# ECUEXT1_23.net
KiCad netlist of a schematic drawn in Altium Designer
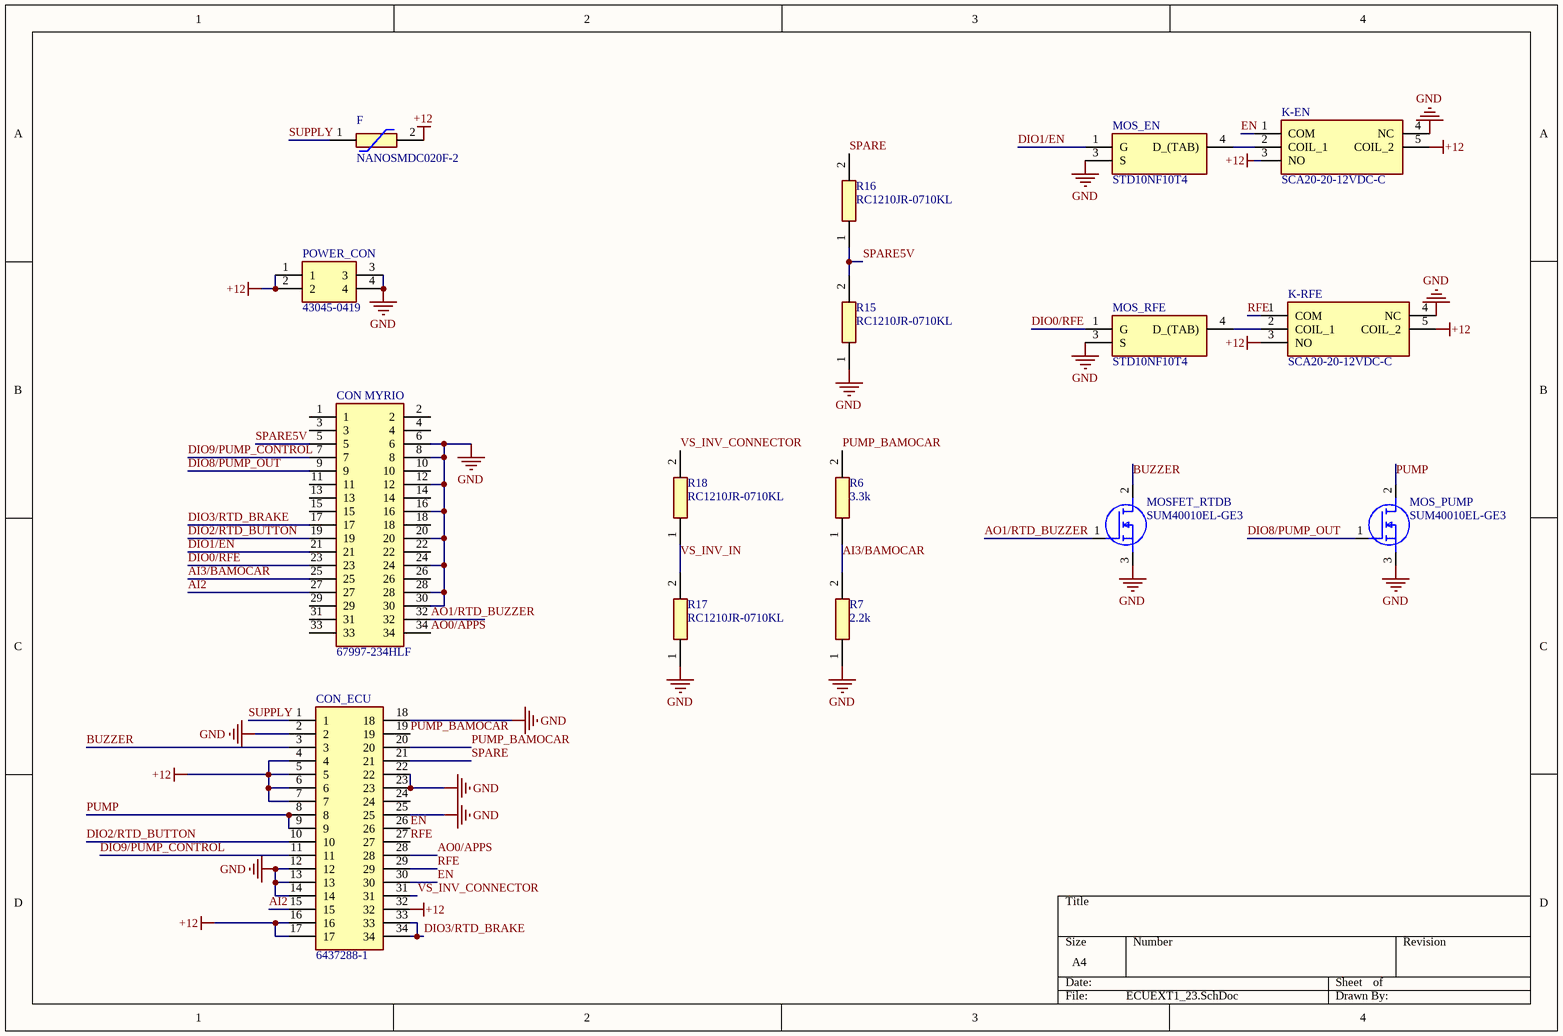
[diagram p0: ECUEXT1_23.SchDoc]

(export (version "E")
  (design (tool "Eeschema 10.0.6"))
  (components
    (comp (ref "CON MYRIO")
      (value "67997-234HLF")
      (footprint "SamacSys:HDRV34W67P254_2X17_4318X483X858P")
      (description "Connector")
      (fields (field (name "MOUSER PART NUMBER") "649-67997-234HLF"))
      (libsource (lib "*") (part "67997-234HLF"))
    )
    (comp (ref "CON_ECU")
      (value "6437288-1")
      (footprint "SamacSys:6437288-1")
      (description "Connector")
      (fields (field (name "MOUSER PART NUMBER") "571-6437288-1"))
      (libsource (lib "SamacSys") (part "6437288-1"))
    )
    (comp (ref "F")
      (value "NANOSMDC020F-2")
      (footprint "SamacSys:NANOSMDC016F2")
      (description "Resettable Fuse")
      (fields (field (name "MOUSER PART NUMBER") "650-NANOSMDC020F-2"))
      (libsource (lib "*") (part "NANOSMDC020F-2"))
    )
    (comp (ref "K-EN")
      (value "SCA20-20-12VDC-C")
      (footprint "SamacSys:SCA202012VDCC")
      (description "Relay or Contactor")
      (libsource (lib "SamacSys") (part "SCA20-20-12VDC-C"))
    )
    (comp (ref "K-RFE")
      (value "SCA20-20-12VDC-C")
      (footprint "SamacSys:SCA202012VDCC")
      (description "Relay or Contactor")
      (libsource (lib "SamacSys") (part "SCA20-20-12VDC-C"))
    )
    (comp (ref "MOSFET_RTDB")
      (value "SUM40010EL-GE3")
      (footprint "SamacSys:SUM40010ELGE3")
      (description "MOSFET (N-Channel)")
      (fields (field (name "MOUSER PART NUMBER") "78-SUM40010EL-GE3"))
      (libsource (lib "SamacSys") (part "SUM40010EL-GE3"))
    )
    (comp (ref "MOS_EN")
      (value "STD10NF10T4")
      (footprint "SamacSys:TO228P972X240-3N")
      (description "Integrated Circuit")
      (fields (field (name "MOUSER PART NUMBER") "511-STD10NF10"))
      (libsource (lib "SamacSys") (part "STD10NF10T4"))
    )
    (comp (ref "MOS_PUMP")
      (value "SUM40010EL-GE3")
      (footprint "SamacSys:SUM40010ELGE3")
      (description "MOSFET (N-Channel)")
      (fields (field (name "MOUSER PART NUMBER") "78-SUM40010EL-GE3"))
      (libsource (lib "SamacSys") (part "SUM40010EL-GE3"))
    )
    (comp (ref "MOS_RFE")
      (value "STD10NF10T4")
      (footprint "SamacSys:TO228P972X240-3N")
      (description "Integrated Circuit")
      (fields (field (name "MOUSER PART NUMBER") "511-STD10NF10"))
      (libsource (lib "SamacSys") (part "STD10NF10T4"))
    )
    (comp (ref "POWER_CON")
      (value "43045-0419")
      (footprint "SamacSys:43045-04YY_181920")
      (description "Connector")
      (fields (field (name "MOUSER PART NUMBER") "538-43045-0419"))
      (libsource (lib "SamacSys") (part "43045-0419"))
    )
    (comp (ref "R6")
      (value "3.3k")
      (footprint "SamacSys:RESC3126X60N")
      (description "Resistor")
      (fields
        (field (name "MANUFACTURER_PART_NUMBER") "RC1210JR-0710KL")
        (field (name "MOUSER PART NUMBER") "603-RC1210JR-0710KL")
      )
      (libsource (lib "*") (part "RC1210JR-0710KL"))
    )
    (comp (ref "R7")
      (value "2.2k")
      (footprint "SamacSys:RESC3126X60N")
      (description "Resistor")
      (fields
        (field (name "MANUFACTURER_PART_NUMBER") "RC1210JR-0710KL")
        (field (name "MOUSER PART NUMBER") "603-RC1210JR-0710KL")
      )
      (libsource (lib "*") (part "RC1210JR-0710KL"))
    )
    (comp (ref "R15")
      (value "RC1210JR-0710KL")
      (footprint "SamacSys:RESC3126X60N")
      (description "Resistor")
      (fields (field (name "MOUSER PART NUMBER") "603-RC1210JR-0710KL"))
      (libsource (lib "SamacSys") (part "RC1210JR-0710KL"))
    )
    (comp (ref "R16")
      (value "RC1210JR-0710KL")
      (footprint "SamacSys:RESC3126X60N")
      (description "Resistor")
      (fields (field (name "MOUSER PART NUMBER") "603-RC1210JR-0710KL"))
      (libsource (lib "SamacSys") (part "RC1210JR-0710KL"))
    )
    (comp (ref "R17")
      (value "RC1210JR-0710KL")
      (footprint "SamacSys:RESC3126X60N")
      (description "Resistor")
      (fields (field (name "MOUSER PART NUMBER") "603-RC1210JR-0710KL"))
      (libsource (lib "SamacSys") (part "RC1210JR-0710KL"))
    )
    (comp (ref "R18")
      (value "RC1210JR-0710KL")
      (footprint "SamacSys:RESC3126X60N")
      (description "Resistor")
      (fields (field (name "MOUSER PART NUMBER") "603-RC1210JR-0710KL"))
      (libsource (lib "SamacSys") (part "RC1210JR-0710KL"))
    )
  )
  (nets
    (net (code "1") (name "+12") (class "Default")
      (node (ref "CON_ECU") (pin "16") (pinfunction "16_16") (pintype "passive"))
      (node (ref "CON_ECU") (pin "17") (pinfunction "17_17") (pintype "passive"))
      (node (ref "CON_ECU") (pin "32") (pinfunction "32_32") (pintype "passive"))
      (node (ref "CON_ECU") (pin "4") (pinfunction "4_4") (pintype "passive"))
      (node (ref "CON_ECU") (pin "5") (pinfunction "5_5") (pintype "passive"))
      (node (ref "CON_ECU") (pin "6") (pinfunction "6_6") (pintype "passive"))
      (node (ref "CON_ECU") (pin "7") (pinfunction "7_7") (pintype "passive"))
      (node (ref "F") (pin "2") (pinfunction "2_2") (pintype "passive"))
      (node (ref "K-EN") (pin "3") (pinfunction "NO_3") (pintype "passive"))
      (node (ref "K-EN") (pin "5") (pinfunction "COIL_2_5") (pintype "passive"))
      (node (ref "K-RFE") (pin "3") (pinfunction "NO_3") (pintype "passive"))
      (node (ref "K-RFE") (pin "5") (pinfunction "COIL_2_5") (pintype "passive"))
      (node (ref "POWER_CON") (pin "1") (pinfunction "1_1") (pintype "passive"))
      (node (ref "POWER_CON") (pin "2") (pinfunction "2_2") (pintype "passive"))
    )
    (net (code "2") (name "/AI2") (class "Default")
      (node (ref "CON MYRIO") (pin "27") (pinfunction "27_27") (pintype "passive"))
      (node (ref "CON_ECU") (pin "15") (pinfunction "15_15") (pintype "passive"))
    )
    (net (code "3") (name "/AI3{slash}BAMOCAR") (class "Default")
      (node (ref "CON MYRIO") (pin "25") (pinfunction "25_25") (pintype "passive"))
      (node (ref "R6") (pin "1") (pinfunction "1_1") (pintype "passive"))
      (node (ref "R7") (pin "2") (pinfunction "2_2") (pintype "passive"))
    )
    (net (code "4") (name "/AO0{slash}APPS") (class "Default")
      (node (ref "CON MYRIO") (pin "34") (pinfunction "34_34") (pintype "passive"))
      (node (ref "CON_ECU") (pin "28") (pinfunction "28_28") (pintype "passive"))
    )
    (net (code "5") (name "/AO1{slash}RTD_BUZZER") (class "Default")
      (node (ref "CON MYRIO") (pin "32") (pinfunction "32_32") (pintype "passive"))
      (node (ref "MOSFET_RTDB") (pin "1") (pinfunction "G_1") (pintype "passive"))
    )
    (net (code "6") (name "/BUZZER") (class "Default")
      (node (ref "CON_ECU") (pin "3") (pinfunction "3_3") (pintype "passive"))
      (node (ref "MOSFET_RTDB") (pin "2") (pinfunction "D_2") (pintype "passive"))
    )
    (net (code "7") (name "/DIO0{slash}RFE") (class "Default")
      (node (ref "CON MYRIO") (pin "23") (pinfunction "23_23") (pintype "passive"))
      (node (ref "MOS_RFE") (pin "1") (pinfunction "G_1") (pintype "passive"))
    )
    (net (code "8") (name "/DIO1{slash}EN") (class "Default")
      (node (ref "CON MYRIO") (pin "21") (pinfunction "21_21") (pintype "passive"))
      (node (ref "MOS_EN") (pin "1") (pinfunction "G_1") (pintype "passive"))
    )
    (net (code "9") (name "/DIO2{slash}RTD_BUTTON") (class "Default")
      (node (ref "CON MYRIO") (pin "19") (pinfunction "19_19") (pintype "passive"))
      (node (ref "CON_ECU") (pin "10") (pinfunction "10_10") (pintype "passive"))
    )
    (net (code "10") (name "/DIO3{slash}RTD_BRAKE") (class "Default")
      (node (ref "CON MYRIO") (pin "17") (pinfunction "17_17") (pintype "passive"))
      (node (ref "CON_ECU") (pin "33") (pinfunction "33_33") (pintype "passive"))
      (node (ref "CON_ECU") (pin "34") (pinfunction "34_34") (pintype "passive"))
    )
    (net (code "11") (name "/DIO8{slash}PUMP_OUT") (class "Default")
      (node (ref "CON MYRIO") (pin "9") (pinfunction "9_9") (pintype "passive"))
      (node (ref "MOS_PUMP") (pin "1") (pinfunction "G_1") (pintype "passive"))
    )
    (net (code "12") (name "/DIO9{slash}PUMP_CONTROL") (class "Default")
      (node (ref "CON MYRIO") (pin "7") (pinfunction "7_7") (pintype "passive"))
      (node (ref "CON_ECU") (pin "11") (pinfunction "11_11") (pintype "passive"))
    )
    (net (code "13") (name "/EN") (class "Default")
      (node (ref "CON_ECU") (pin "26") (pinfunction "26_26") (pintype "passive"))
      (node (ref "CON_ECU") (pin "30") (pinfunction "30_30") (pintype "passive"))
      (node (ref "K-EN") (pin "1") (pinfunction "COM_1") (pintype "passive"))
    )
    (net (code "14") (name "/PUMP") (class "Default")
      (node (ref "CON_ECU") (pin "8") (pinfunction "8_8") (pintype "passive"))
      (node (ref "CON_ECU") (pin "9") (pinfunction "9_9") (pintype "passive"))
      (node (ref "MOS_PUMP") (pin "2") (pinfunction "D_2") (pintype "passive"))
    )
    (net (code "15") (name "/PUMP_BAMOCAR") (class "Default")
      (node (ref "CON_ECU") (pin "19") (pinfunction "19_19") (pintype "passive"))
      (node (ref "CON_ECU") (pin "20") (pinfunction "20_20") (pintype "passive"))
      (node (ref "R6") (pin "2") (pinfunction "2_2") (pintype "passive"))
    )
    (net (code "16") (name "/RFE") (class "Default")
      (node (ref "CON_ECU") (pin "27") (pinfunction "27_27") (pintype "passive"))
      (node (ref "CON_ECU") (pin "29") (pinfunction "29_29") (pintype "passive"))
      (node (ref "K-RFE") (pin "1") (pinfunction "COM_1") (pintype "passive"))
    )
    (net (code "17") (name "/SPARE") (class "Default")
      (node (ref "CON_ECU") (pin "21") (pinfunction "21_21") (pintype "passive"))
      (node (ref "R16") (pin "2") (pinfunction "2_2") (pintype "passive"))
    )
    (net (code "18") (name "/SPARE5V") (class "Default")
      (node (ref "CON MYRIO") (pin "5") (pinfunction "5_5") (pintype "passive"))
      (node (ref "R15") (pin "2") (pinfunction "2_2") (pintype "passive"))
      (node (ref "R16") (pin "1") (pinfunction "1_1") (pintype "passive"))
    )
    (net (code "19") (name "/SUPPLY") (class "Default")
      (node (ref "CON_ECU") (pin "1") (pinfunction "1_1") (pintype "passive"))
      (node (ref "F") (pin "1") (pinfunction "1_1") (pintype "passive"))
    )
    (net (code "20") (name "/VS_INV_CONNECTOR") (class "Default")
      (node (ref "CON_ECU") (pin "31") (pinfunction "31_31") (pintype "passive"))
      (node (ref "R18") (pin "2") (pinfunction "2_2") (pintype "passive"))
    )
    (net (code "21") (name "/VS_INV_IN") (class "Default")
      (node (ref "R17") (pin "2") (pinfunction "2_2") (pintype "passive"))
      (node (ref "R18") (pin "1") (pinfunction "1_1") (pintype "passive"))
    )
    (net (code "22") (name "GND") (class "Default")
      (node (ref "CON MYRIO") (pin "12") (pinfunction "12_12") (pintype "passive"))
      (node (ref "CON MYRIO") (pin "16") (pinfunction "16_16") (pintype "passive"))
      (node (ref "CON MYRIO") (pin "20") (pinfunction "20_20") (pintype "passive"))
      (node (ref "CON MYRIO") (pin "24") (pinfunction "24_24") (pintype "passive"))
      (node (ref "CON MYRIO") (pin "28") (pinfunction "28_28") (pintype "passive"))
      (node (ref "CON MYRIO") (pin "30") (pinfunction "30_30") (pintype "passive"))
      (node (ref "CON MYRIO") (pin "6") (pinfunction "6_6") (pintype "passive"))
      (node (ref "CON MYRIO") (pin "8") (pinfunction "8_8") (pintype "passive"))
      (node (ref "CON_ECU") (pin "12") (pinfunction "12_12") (pintype "passive"))
      (node (ref "CON_ECU") (pin "13") (pinfunction "13_13") (pintype "passive"))
      (node (ref "CON_ECU") (pin "14") (pinfunction "14_14") (pintype "passive"))
      (node (ref "CON_ECU") (pin "18") (pinfunction "18_18") (pintype "passive"))
      (node (ref "CON_ECU") (pin "2") (pinfunction "2_2") (pintype "passive"))
      (node (ref "CON_ECU") (pin "22") (pinfunction "22_22") (pintype "passive"))
      (node (ref "CON_ECU") (pin "23") (pinfunction "23_23") (pintype "passive"))
      (node (ref "CON_ECU") (pin "25") (pinfunction "25_25") (pintype "passive"))
      (node (ref "K-EN") (pin "4") (pinfunction "NC_4") (pintype "passive"))
      (node (ref "K-RFE") (pin "4") (pinfunction "NC_4") (pintype "passive"))
      (node (ref "MOSFET_RTDB") (pin "3") (pinfunction "S_3") (pintype "passive"))
      (node (ref "MOS_EN") (pin "3") (pinfunction "S_3") (pintype "passive"))
      (node (ref "MOS_PUMP") (pin "3") (pinfunction "S_3") (pintype "passive"))
      (node (ref "MOS_RFE") (pin "3") (pinfunction "S_3") (pintype "passive"))
      (node (ref "POWER_CON") (pin "3") (pinfunction "3_3") (pintype "passive"))
      (node (ref "POWER_CON") (pin "4") (pinfunction "4_4") (pintype "passive"))
      (node (ref "R15") (pin "1") (pinfunction "1_1") (pintype "passive"))
      (node (ref "R17") (pin "1") (pinfunction "1_1") (pintype "passive"))
      (node (ref "R7") (pin "1") (pinfunction "1_1") (pintype "passive"))
    )
    (net (code "23") (name "Net-(K-EN-COIL_1)") (class "Default")
      (node (ref "K-EN") (pin "2") (pinfunction "COIL_1_2") (pintype "passive"))
      (node (ref "MOS_EN") (pin "4") (pinfunction "D_(TAB)_4") (pintype "passive"))
    )
    (net (code "24") (name "Net-(K-RFE-COIL_1)") (class "Default")
      (node (ref "K-RFE") (pin "2") (pinfunction "COIL_1_2") (pintype "passive"))
      (node (ref "MOS_RFE") (pin "4") (pinfunction "D_(TAB)_4") (pintype "passive"))
    )
    (net (code "25") (name "unconnected-(CON MYRIO-Pad1)") (class "Default")
      (node (ref "CON MYRIO") (pin "1") (pinfunction "1_1") (pintype "passive"))
    )
    (net (code "26") (name "unconnected-(CON MYRIO-Pad2)") (class "Default")
      (node (ref "CON MYRIO") (pin "2") (pinfunction "2_2") (pintype "passive"))
    )
    (net (code "27") (name "unconnected-(CON MYRIO-Pad3)") (class "Default")
      (node (ref "CON MYRIO") (pin "3") (pinfunction "3_3") (pintype "passive"))
    )
    (net (code "28") (name "unconnected-(CON MYRIO-Pad4)") (class "Default")
      (node (ref "CON MYRIO") (pin "4") (pinfunction "4_4") (pintype "passive"))
    )
    (net (code "29") (name "unconnected-(CON MYRIO-Pad10)") (class "Default")
      (node (ref "CON MYRIO") (pin "10") (pinfunction "10_10") (pintype "passive"))
    )
    (net (code "30") (name "unconnected-(CON MYRIO-Pad11)") (class "Default")
      (node (ref "CON MYRIO") (pin "11") (pinfunction "11_11") (pintype "passive"))
    )
    (net (code "31") (name "unconnected-(CON MYRIO-Pad13)") (class "Default")
      (node (ref "CON MYRIO") (pin "13") (pinfunction "13_13") (pintype "passive"))
    )
    (net (code "32") (name "unconnected-(CON MYRIO-Pad14)") (class "Default")
      (node (ref "CON MYRIO") (pin "14") (pinfunction "14_14") (pintype "passive"))
    )
    (net (code "33") (name "unconnected-(CON MYRIO-Pad15)") (class "Default")
      (node (ref "CON MYRIO") (pin "15") (pinfunction "15_15") (pintype "passive"))
    )
    (net (code "34") (name "unconnected-(CON MYRIO-Pad18)") (class "Default")
      (node (ref "CON MYRIO") (pin "18") (pinfunction "18_18") (pintype "passive"))
    )
    (net (code "35") (name "unconnected-(CON MYRIO-Pad22)") (class "Default")
      (node (ref "CON MYRIO") (pin "22") (pinfunction "22_22") (pintype "passive"))
    )
    (net (code "36") (name "unconnected-(CON MYRIO-Pad26)") (class "Default")
      (node (ref "CON MYRIO") (pin "26") (pinfunction "26_26") (pintype "passive"))
    )
    (net (code "37") (name "unconnected-(CON MYRIO-Pad29)") (class "Default")
      (node (ref "CON MYRIO") (pin "29") (pinfunction "29_29") (pintype "passive"))
    )
    (net (code "38") (name "unconnected-(CON MYRIO-Pad31)") (class "Default")
      (node (ref "CON MYRIO") (pin "31") (pinfunction "31_31") (pintype "passive"))
    )
    (net (code "39") (name "unconnected-(CON MYRIO-Pad33)") (class "Default")
      (node (ref "CON MYRIO") (pin "33") (pinfunction "33_33") (pintype "passive"))
    )
    (net (code "40") (name "unconnected-(CON_ECU-Pad24)") (class "Default")
      (node (ref "CON_ECU") (pin "24") (pinfunction "24_24") (pintype "passive"))
    )
  )
)
